# MB1297_POWER.net
KiCad netlist of a schematic drawn in Altium Designer
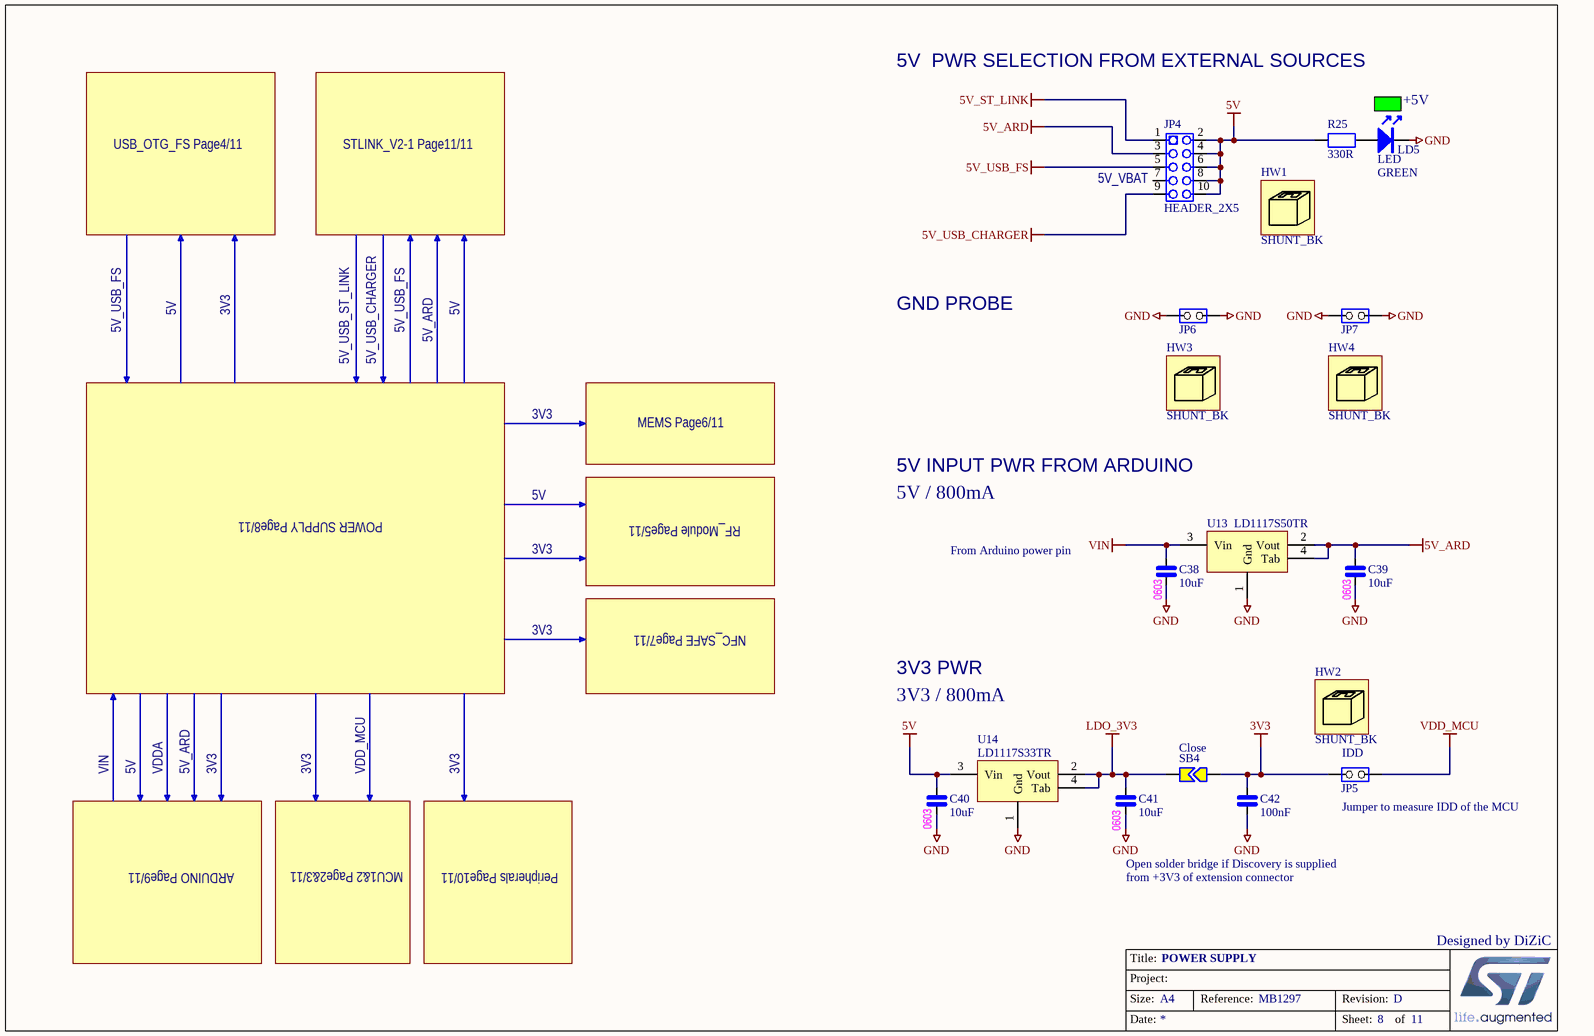
[diagram p0: MB1297_POWER.SchDoc]

(export (version "E")
  (design (tool "Eeschema 10.0.6"))
  (components
    (comp (ref "C38")
      (value "10uF")
      (footprint "0603_CAP_NPOL")
      (description "Capacitor_not polarized")
      (libsource (lib "ST_Lib3D") (part "CAP_NPOL"))
    )
    (comp (ref "C39")
      (value "10uF")
      (footprint "0603_CAP_NPOL")
      (description "Capacitor_not polarized")
      (libsource (lib "ST_Lib3D") (part "CAP_NPOL"))
    )
    (comp (ref "C40")
      (value "10uF")
      (footprint "0603_CAP_NPOL")
      (description "Capacitor_not polarized")
      (libsource (lib "ST_Lib3D") (part "CAP_NPOL"))
    )
    (comp (ref "C41")
      (value "10uF")
      (footprint "0603_CAP_NPOL")
      (description "Capacitor_not polarized")
      (libsource (lib "ST_Lib3D") (part "CAP_NPOL"))
    )
    (comp (ref "C42")
      (value "100nF")
      (footprint "0402_CAP_NPOL")
      (description "Capacitor_not polarized")
      (libsource (lib "ST_Lib3D") (part "CAP_NPOL"))
    )
    (comp (ref "HW1")
      (value "SHUNT_BK")
      (description "SHUNT 2.54mm BLACK")
      (libsource (lib "MCD_TEMP_PCH") (part "Shunt 2.54mm"))
    )
    (comp (ref "HW2")
      (value "SHUNT_BK")
      (description "SHUNT 2.54mm BLACK")
      (libsource (lib "MCD_TEMP_PCH") (part "Shunt 2.54mm"))
    )
    (comp (ref "HW3")
      (value "SHUNT_BK")
      (description "SHUNT 2.54mm BLACK")
      (libsource (lib "MCD_TEMP_PCH") (part "Shunt 2.54mm"))
    )
    (comp (ref "HW4")
      (value "SHUNT_BK")
      (description "SHUNT 2.54mm BLACK")
      (libsource (lib "MCD_TEMP_PCH") (part "Shunt 2.54mm"))
    )
    (comp (ref "JP4")
      (value "HEADER_2X5")
      (footprint "Header M 2x5x2.54 TH V")
      (libsource (lib "ST_Lib3D") (part "HEADER_2X5"))
    )
    (comp (ref "JP5")
      (value "Jumper_2.54mm")
      (footprint "CON_SAMTEC_TSW-102-07-G-S")
      (description "Connector jumper 1 position")
      (libsource (lib "MCD_TEMP_PCH") (part "TSW-102-07-x-S"))
    )
    (comp (ref "JP6")
      (value "Jumper_2.54mm")
      (footprint "CON_SAMTEC_TSW-102-07-G-S")
      (description "Connector jumper 1 position")
      (libsource (lib "MCD_TEMP_PCH") (part "TSW-102-07-x-S"))
    )
    (comp (ref "JP7")
      (value "Jumper_2.54mm")
      (footprint "CON_SAMTEC_TSW-102-07-G-S")
      (description "Connector jumper 1 position")
      (libsource (lib "MCD_TEMP_PCH") (part "TSW-102-07-x-S"))
    )
    (comp (ref "LD5")
      (value "LED")
      (footprint "0603_LED_GREEN")
      (description "Light-Emitting Diode")
      (fields (field (name "COLOR") "GREEN"))
      (libsource (lib "ST_Lib3D") (part "LED"))
    )
    (comp (ref "R25")
      (value "330R")
      (footprint "0402_RES")
      (description "Resistor")
      (libsource (lib "Lib3D_Altium10_Schlib") (part "RES"))
    )
    (comp (ref "SB4")
      (value "Close")
      (footprint "SB")
      (description "Solder Jumper")
      (fields (field (name "PUBLISHER") "Altium Limited"))
      (libsource (lib "Lib3D_Altium10_Schlib") (part "Strap2"))
    )
    (comp (ref "U13")
      (value "LD1117S50TR")
      (footprint "REG_SOT223-TAB")
      (description "IC REG LDO 5V 0.8A SOT223")
      (libsource (lib "MCD_TEMP_PCH") (part "LD1117S50TR"))
    )
    (comp (ref "U14")
      (value "LD1117S33TR")
      (footprint "REG_SOT223-TAB")
      (description "LOW DROP FIXED AND ADJUSTABLE POSITIVE VOLTAGE REGULATORS (3.3 Volts)")
      (libsource (lib "MCD_TEMP_PCH") (part "LD1117S33TR"))
    )
  )
  (nets
    (net (code "1") (name "3V3") (class "Default")
      (node (ref "C42") (pin "1") (pinfunction "1_1") (pintype "passive"))
      (node (ref "JP5") (pin "1") (pinfunction "COMMON_1") (pintype "passive"))
      (node (ref "SB4") (pin "2") (pinfunction "2_2") (pintype "passive"))
    )
    (net (code "2") (name "5V") (class "Default")
      (node (ref "C40") (pin "1") (pinfunction "1_1") (pintype "passive"))
      (node (ref "JP4") (pin "10") (pinfunction "10_10") (pintype "passive"))
      (node (ref "JP4") (pin "2") (pinfunction "2_2") (pintype "passive"))
      (node (ref "JP4") (pin "4") (pinfunction "4_4") (pintype "passive"))
      (node (ref "JP4") (pin "6") (pinfunction "6_6") (pintype "passive"))
      (node (ref "JP4") (pin "8") (pinfunction "8_8") (pintype "passive"))
      (node (ref "R25") (pin "1") (pinfunction "1_1") (pintype "passive"))
      (node (ref "U14") (pin "3") (pinfunction "Vin_3") (pintype "passive"))
    )
    (net (code "3") (name "5V_ARD") (class "Default")
      (node (ref "C39") (pin "1") (pinfunction "1_1") (pintype "passive"))
      (node (ref "JP4") (pin "3") (pinfunction "3_3") (pintype "passive"))
      (node (ref "U13") (pin "2") (pinfunction "Vout_2") (pintype "passive"))
      (node (ref "U13") (pin "4") (pinfunction "Tab_4") (pintype "passive"))
    )
    (net (code "4") (name "5V_ST_LINK") (class "Default")
      (node (ref "JP4") (pin "1") (pinfunction "1_1") (pintype "passive"))
    )
    (net (code "5") (name "5V_USB_CHARGER") (class "Default")
      (node (ref "JP4") (pin "9") (pinfunction "9_9") (pintype "passive"))
    )
    (net (code "6") (name "5V_USB_FS") (class "Default")
      (node (ref "JP4") (pin "5") (pinfunction "5_5") (pintype "passive"))
    )
    (net (code "7") (name "GND") (class "Default")
      (node (ref "C38") (pin "2") (pinfunction "2_2") (pintype "passive"))
      (node (ref "C39") (pin "2") (pinfunction "2_2") (pintype "passive"))
      (node (ref "C40") (pin "2") (pinfunction "2_2") (pintype "passive"))
      (node (ref "C41") (pin "2") (pinfunction "2_2") (pintype "passive"))
      (node (ref "C42") (pin "2") (pinfunction "2_2") (pintype "passive"))
      (node (ref "JP6") (pin "1") (pinfunction "COMMON_1") (pintype "passive"))
      (node (ref "JP6") (pin "2") (pinfunction "NO_2") (pintype "passive"))
      (node (ref "JP7") (pin "1") (pinfunction "COMMON_1") (pintype "passive"))
      (node (ref "JP7") (pin "2") (pinfunction "NO_2") (pintype "passive"))
      (node (ref "LD5") (pin "K") (pinfunction "K_K") (pintype "passive"))
      (node (ref "U13") (pin "1") (pinfunction "Gnd_1") (pintype "passive"))
      (node (ref "U14") (pin "1") (pinfunction "Gnd_1") (pintype "passive"))
    )
    (net (code "8") (name "LDO_3V3") (class "Default")
      (node (ref "C41") (pin "1") (pinfunction "1_1") (pintype "passive"))
      (node (ref "SB4") (pin "1") (pinfunction "1_1") (pintype "passive"))
      (node (ref "U14") (pin "2") (pinfunction "Vout_2") (pintype "passive"))
      (node (ref "U14") (pin "4") (pinfunction "Tab_4") (pintype "passive"))
    )
    (net (code "9") (name "Net-(LD5-PadA)") (class "Default")
      (node (ref "LD5") (pin "A") (pinfunction "A_A") (pintype "passive"))
      (node (ref "R25") (pin "2") (pinfunction "2_2") (pintype "passive"))
    )
    (net (code "10") (name "VDD_MCU") (class "Default")
      (node (ref "JP5") (pin "2") (pinfunction "NO_2") (pintype "passive"))
    )
    (net (code "11") (name "VIN") (class "Default")
      (node (ref "C38") (pin "1") (pinfunction "1_1") (pintype "passive"))
      (node (ref "U13") (pin "3") (pinfunction "Vin_3") (pintype "passive"))
    )
    (net (code "12") (name "unconnected-(JP4-Pad7)") (class "Default")
      (node (ref "JP4") (pin "7") (pinfunction "7_7") (pintype "passive"))
    )
  )
)
